# Main.net
KiCad netlist of a schematic drawn in Altium Designer
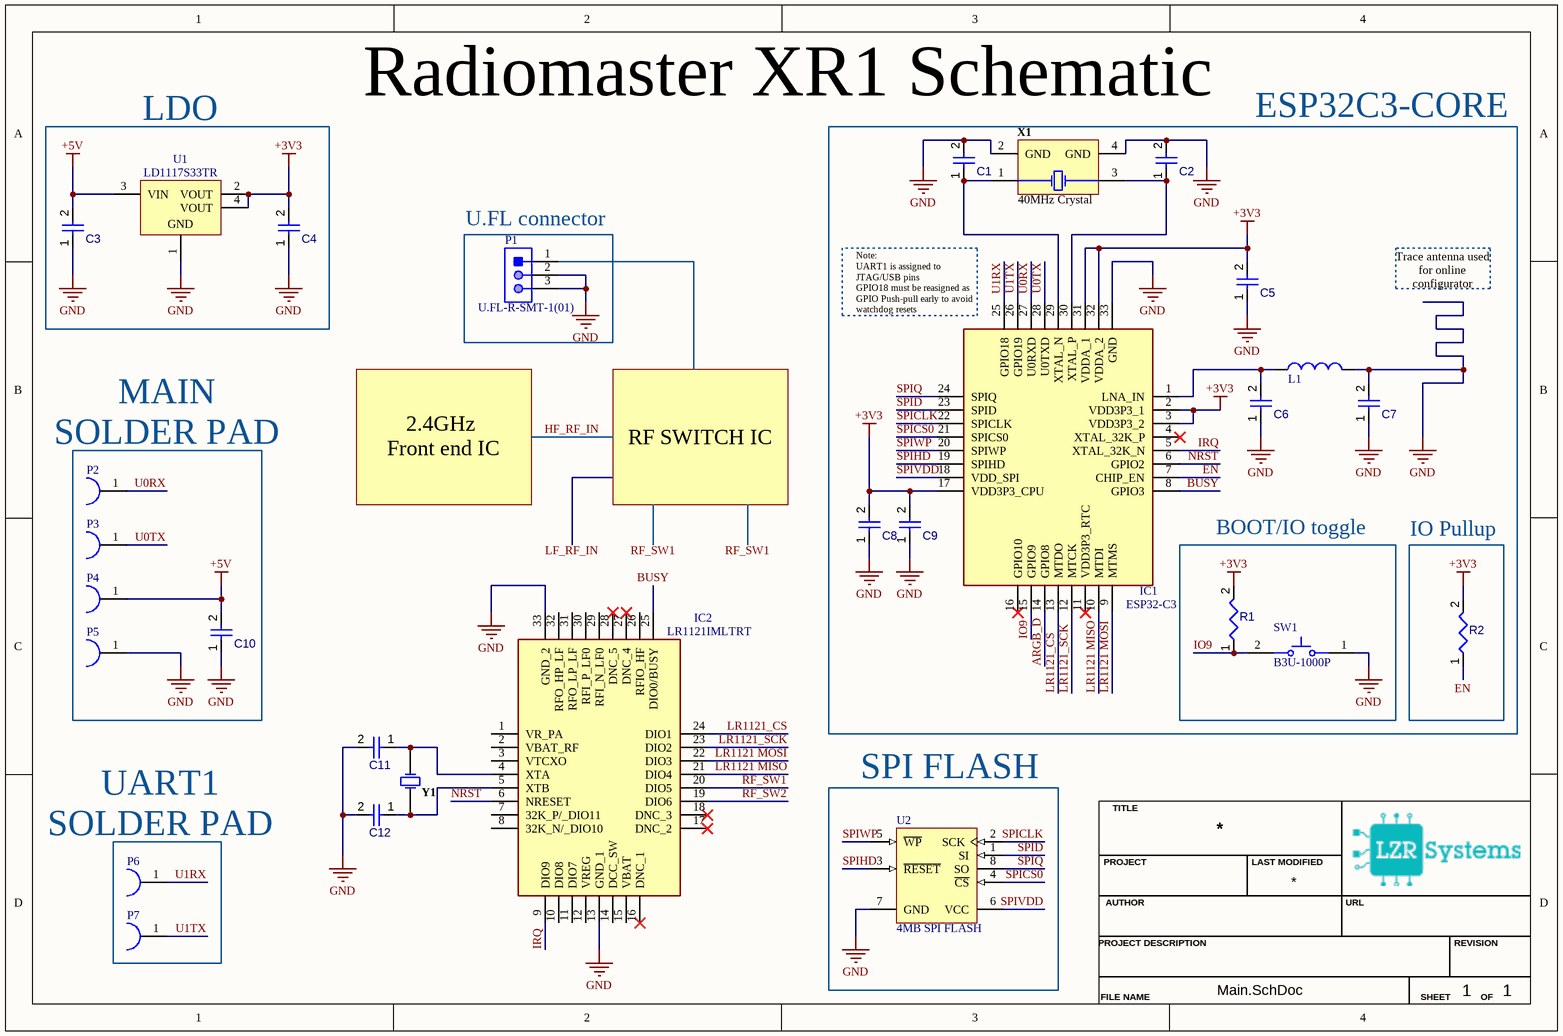
[diagram p0: Main.SchDoc]

(export (version "E")
  (design (tool "Eeschema 10.0.6"))
  (components
    (comp (ref "C1")
      (value "Capacitors")
      (description "Capacitor")
      (libsource (lib "Sandor Lazar") (part "CAP-NP-2"))
    )
    (comp (ref "C2")
      (value "Capacitors")
      (description "Capacitor")
      (libsource (lib "Sandor Lazar") (part "CAP-NP-2"))
    )
    (comp (ref "C3")
      (value "Capacitors")
      (description "Capacitor")
      (libsource (lib "Sandor Lazar") (part "CAP-NP-2"))
    )
    (comp (ref "C4")
      (value "Capacitors")
      (description "Capacitor")
      (libsource (lib "Sandor Lazar") (part "CAP-NP-2"))
    )
    (comp (ref "C5")
      (value "Capacitors")
      (description "Capacitor")
      (libsource (lib "Sandor Lazar") (part "CAP-NP-2"))
    )
    (comp (ref "C6")
      (value "Capacitors")
      (description "Capacitor")
      (libsource (lib "Sandor Lazar") (part "CAP-NP-2"))
    )
    (comp (ref "C7")
      (value "Capacitors")
      (description "Capacitor")
      (libsource (lib "Sandor Lazar") (part "CAP-NP-2"))
    )
    (comp (ref "C8")
      (value "Capacitors")
      (description "Capacitor")
      (libsource (lib "Sandor Lazar") (part "CAP-NP-2"))
    )
    (comp (ref "C9")
      (value "Capacitors")
      (description "Capacitor")
      (libsource (lib "Sandor Lazar") (part "CAP-NP-2"))
    )
    (comp (ref "C10")
      (value "Capacitors")
      (description "Capacitor")
      (libsource (lib "Sandor Lazar") (part "CAP-NP-2"))
    )
    (comp (ref "C11")
      (value "Capacitors")
      (description "Capacitor")
      (libsource (lib "Sandor Lazar") (part "CAP-NP-2"))
    )
    (comp (ref "C12")
      (value "Capacitors")
      (description "Capacitor")
      (libsource (lib "Sandor Lazar") (part "CAP-NP-2"))
    )
    (comp (ref "IC1")
      (value "ESP32-C3")
      (footprint "SamacSys:QFN50P500X500X90-33N-D")
      (description "Integrated Circuit")
      (fields (field (name "MOUSER PART NUMBER") "356-ESP32-C3"))
      (libsource (lib "SamacSys") (part "ESP32-C3"))
    )
    (comp (ref "IC2")
      (value "LR1121IMLTRT")
      (footprint "SamacSys:QFN50P500X500X100-33N-D")
      (description "Integrated Circuit")
      (fields (field (name "MOUSER PART NUMBER") "947-LR1121IMLTRT"))
      (libsource (lib "*") (part "LR1121IMLTRT"))
    )
    (comp (ref "L1") (value "Inductors") (libsource (lib "Sandor Lazar") (part "IND-2")))
    (comp (ref "P1")
      (value "U.FL-R-SMT-1(01)")
      (footprint "HRS-U.FL-R-SMT-3_V")
      (description "Rf Connectors / Coaxial Connectors SMT Ml Rec Au 50 Ohm W/anti Sldr Wicking")
      (libsource (lib "Sandor Lazar") (part "CN-1P-M-R3"))
    )
    (comp (ref "P2")
      (value "Solder Pad 2x1.5mm")
      (footprint "Solder Pad 2x1.5mm-Footprint-1")
      (description "Solder Pad 2x1.5mm, 0.5mm hole")
      (libsource (lib "Sandor Lazar") (part "Solder Pad 2x1.5mm"))
    )
    (comp (ref "P3")
      (value "Solder Pad 2x1.5mm")
      (footprint "Solder Pad 2x1.5mm-Footprint-1")
      (description "Solder Pad 2x1.5mm, 0.5mm hole")
      (libsource (lib "Sandor Lazar") (part "Solder Pad 2x1.5mm"))
    )
    (comp (ref "P4")
      (value "Solder Pad 2x1.5mm")
      (footprint "Solder Pad 2x1.5mm-Footprint-1")
      (description "Solder Pad 2x1.5mm, 0.5mm hole")
      (libsource (lib "Sandor Lazar") (part "Solder Pad 2x1.5mm"))
    )
    (comp (ref "P5")
      (value "Solder Pad 2x1.5mm")
      (footprint "Solder Pad 2x1.5mm-Footprint-1")
      (description "Solder Pad 2x1.5mm, 0.5mm hole")
      (libsource (lib "Sandor Lazar") (part "Solder Pad 2x1.5mm"))
    )
    (comp (ref "P6")
      (value "Solder Pad 2x1.5mm")
      (footprint "Solder Pad 2x1.5mm-Footprint-1")
      (description "Solder Pad 2x1.5mm, 0.5mm hole")
      (libsource (lib "Sandor Lazar") (part "Solder Pad 2x1.5mm"))
    )
    (comp (ref "P7")
      (value "Solder Pad 2x1.5mm")
      (footprint "Solder Pad 2x1.5mm-Footprint-1")
      (description "Solder Pad 2x1.5mm, 0.5mm hole")
      (libsource (lib "Sandor Lazar") (part "Solder Pad 2x1.5mm"))
    )
    (comp (ref "R1")
      (value "Resistors")
      (description "Resistor")
      (libsource (lib "Sandor Lazar") (part "RES-2"))
    )
    (comp (ref "R2")
      (value "Resistors")
      (description "Resistor")
      (libsource (lib "Sandor Lazar") (part "RES-2"))
    )
    (comp (ref "SW1")
      (value "B3U-1000P")
      (footprint "OMRON-B3U-1000_V")
      (description "Tactile Switch, SPST-NO, 0.05 A, 12 V, -25 to 70 degC, 2-Pin SMD, RoHS, Tape and Reel")
      (fields (field (name "MANUFACTURER") "Omron Electronic Components"))
      (libsource (lib "Sandor Lazar") (part "SW-SPST-NO-2"))
    )
    (comp (ref "U1")
      (value "LD1117S33TR")
      (footprint "STM-SOT-223_M")
      (fields (field (name "POWER") "12W") (field (name "MANUFACTURER") "STMicroelectronics"))
      (libsource (lib "Sandor Lazar") (part "STM-LD1117-SOT223-4"))
    )
    (comp (ref "U2")
      (value "4MB SPI FLASH")
      (footprint "ADST-8S1_M")
      (description "SPI Serial Flash Memory, 4-Mbit, 1.65 to 3.6 V, -40 to 85 degC, 8-Pin SOIC (8S1), RoHS, Tube")
      (fields (field (name "MANUFACTURER") "Adesto"))
      (libsource (lib "Sandor Lazar") (part "ADST-AT45DB041E-SOIC-8"))
    )
    (comp (ref "X1")
      (value "40MHz Crystal")
      (footprint "ABRA-ABM3B-4_V")
      (description "Ceramic SMD Crystal, 40 MHz, +/- 20 ppm, 18 pF, -20 to 70 degC, 4-Pin SMD, RoHS, Tape and Reel")
      (fields (field (name "TOLERANCE") "20ppm") (field (name "MANUFACTURER") "Abracon"))
      (libsource (lib "Sandor Lazar") (part "XTAL-1-3-4"))
    )
    (comp (ref "Y1")
      (value "Crystals & Oscillators")
      (description "Crystal")
      (libsource (lib "Sandor Lazar") (part "XTAL-2"))
    )
  )
  (nets
    (net (code "1") (name "+3V3") (class "Default")
      (node (ref "C4") (pin "2") (pinfunction "2_2") (pintype "passive"))
      (node (ref "C5") (pin "2") (pinfunction "2_2") (pintype "passive"))
      (node (ref "C8") (pin "2") (pinfunction "2_2") (pintype "passive"))
      (node (ref "C9") (pin "2") (pinfunction "2_2") (pintype "passive"))
      (node (ref "IC1") (pin "17") (pinfunction "VDD3P3_CPU_17") (pintype "passive"))
      (node (ref "IC1") (pin "2") (pinfunction "VDD3P3_1_2") (pintype "passive"))
      (node (ref "IC1") (pin "3") (pinfunction "VDD3P3_2_3") (pintype "passive"))
      (node (ref "IC1") (pin "31") (pinfunction "VDDA_1_31") (pintype "passive"))
      (node (ref "IC1") (pin "32") (pinfunction "VDDA_2_32") (pintype "passive"))
      (node (ref "R1") (pin "2") (pinfunction "2_2") (pintype "passive"))
      (node (ref "R2") (pin "2") (pinfunction "2_2") (pintype "passive"))
      (node (ref "U1") (pin "2") (pinfunction "VOUT_2") (pintype "power_in"))
      (node (ref "U1") (pin "4") (pinfunction "VOUT_4") (pintype "power_in"))
    )
    (net (code "2") (name "+5V") (class "Default")
      (node (ref "C10") (pin "2") (pinfunction "2_2") (pintype "passive"))
      (node (ref "C3") (pin "2") (pinfunction "2_2") (pintype "passive"))
      (node (ref "P4") (pin "1") (pinfunction "1_1") (pintype "passive"))
      (node (ref "U1") (pin "3") (pinfunction "VIN_3") (pintype "power_in"))
    )
    (net (code "3") (name "/ARGB_D") (class "Default")
      (node (ref "IC1") (pin "14") (pinfunction "GPIO8_14") (pintype "passive"))
    )
    (net (code "4") (name "/BUSY") (class "Default")
      (node (ref "IC1") (pin "8") (pinfunction "GPIO3_8") (pintype "passive"))
      (node (ref "IC2") (pin "25") (pinfunction "DIO0/BUSY_25") (pintype "passive"))
    )
    (net (code "5") (name "/EN") (class "Default")
      (node (ref "IC1") (pin "7") (pinfunction "CHIP_EN_7") (pintype "passive"))
      (node (ref "R2") (pin "1") (pinfunction "1_1") (pintype "passive"))
    )
    (net (code "7") (name "/IO9") (class "Default")
      (node (ref "IC1") (pin "15") (pinfunction "GPIO9_15") (pintype "passive"))
      (node (ref "R1") (pin "1") (pinfunction "1_1") (pintype "passive"))
      (node (ref "SW1") (pin "2") (pinfunction "2_2") (pintype "passive"))
    )
    (net (code "8") (name "/IRQ") (class "Default")
      (node (ref "IC1") (pin "5") (pinfunction "XTAL_32K_N_5") (pintype "passive"))
      (node (ref "IC2") (pin "9") (pinfunction "DIO9_9") (pintype "passive"))
    )
    (net (code "10") (name "/LR1121 MISO") (class "Default")
      (node (ref "IC1") (pin "10") (pinfunction "MTDI_10") (pintype "passive"))
      (node (ref "IC2") (pin "21") (pinfunction "DIO4_21") (pintype "passive"))
    )
    (net (code "11") (name "/LR1121 MOSI") (class "Default")
      (node (ref "IC1") (pin "9") (pinfunction "MTMS_9") (pintype "passive"))
      (node (ref "IC2") (pin "22") (pinfunction "DIO3_22") (pintype "passive"))
    )
    (net (code "12") (name "/LR1121_CS") (class "Default")
      (node (ref "IC1") (pin "13") (pinfunction "MTDO_13") (pintype "passive"))
      (node (ref "IC2") (pin "24") (pinfunction "DIO1_24") (pintype "passive"))
    )
    (net (code "13") (name "/LR1121_SCK") (class "Default")
      (node (ref "IC1") (pin "12") (pinfunction "MTCK_12") (pintype "passive"))
      (node (ref "IC2") (pin "23") (pinfunction "DIO2_23") (pintype "passive"))
    )
    (net (code "14") (name "/NRST") (class "Default")
      (node (ref "IC1") (pin "6") (pinfunction "GPIO2_6") (pintype "passive"))
      (node (ref "IC2") (pin "6") (pinfunction "NRESET_6") (pintype "passive"))
    )
    (net (code "15") (name "/RF_SW1") (class "Default")
      (node (ref "IC2") (pin "20") (pinfunction "DIO5_20") (pintype "passive"))
    )
    (net (code "16") (name "/RF_SW2") (class "Default")
      (node (ref "IC2") (pin "19") (pinfunction "DIO6_19") (pintype "passive"))
    )
    (net (code "17") (name "/SPICLK") (class "Default")
      (node (ref "IC1") (pin "22") (pinfunction "SPICLK_22") (pintype "passive"))
      (node (ref "U2") (pin "2") (pinfunction "SCK_2") (pintype "input"))
    )
    (net (code "18") (name "/SPICS0") (class "Default")
      (node (ref "IC1") (pin "21") (pinfunction "SPICS0_21") (pintype "passive"))
      (node (ref "U2") (pin "4") (pinfunction "~{CS}_4") (pintype "input"))
    )
    (net (code "19") (name "/SPID") (class "Default")
      (node (ref "IC1") (pin "23") (pinfunction "SPID_23") (pintype "passive"))
      (node (ref "U2") (pin "1") (pinfunction "SI_1") (pintype "input"))
    )
    (net (code "20") (name "/SPIHD") (class "Default")
      (node (ref "IC1") (pin "19") (pinfunction "SPIHD_19") (pintype "passive"))
      (node (ref "U2") (pin "3") (pinfunction "~{RESET}_3") (pintype "input"))
    )
    (net (code "21") (name "/SPIQ") (class "Default")
      (node (ref "IC1") (pin "24") (pinfunction "SPIQ_24") (pintype "passive"))
      (node (ref "U2") (pin "8") (pinfunction "SO_8") (pintype "tri_state"))
    )
    (net (code "22") (name "/SPIVDD") (class "Default")
      (node (ref "IC1") (pin "18") (pinfunction "VDD_SPI_18") (pintype "passive"))
      (node (ref "U2") (pin "6") (pinfunction "VCC_6") (pintype "power_in"))
    )
    (net (code "23") (name "/SPIWP") (class "Default")
      (node (ref "IC1") (pin "20") (pinfunction "SPIWP_20") (pintype "passive"))
      (node (ref "U2") (pin "5") (pinfunction "~{WP}_5") (pintype "input"))
    )
    (net (code "24") (name "/U0RX") (class "Default")
      (node (ref "IC1") (pin "27") (pinfunction "U0RXD_27") (pintype "passive"))
      (node (ref "P2") (pin "1") (pinfunction "1_1") (pintype "passive"))
    )
    (net (code "25") (name "/U0TX") (class "Default")
      (node (ref "IC1") (pin "28") (pinfunction "U0TXD_28") (pintype "passive"))
      (node (ref "P3") (pin "1") (pinfunction "1_1") (pintype "passive"))
    )
    (net (code "26") (name "/U1RX") (class "Default")
      (node (ref "IC1") (pin "25") (pinfunction "GPIO18_25") (pintype "passive"))
      (node (ref "P6") (pin "1") (pinfunction "1_1") (pintype "passive"))
    )
    (net (code "27") (name "/U1TX") (class "Default")
      (node (ref "IC1") (pin "26") (pinfunction "GPIO19_26") (pintype "passive"))
      (node (ref "P7") (pin "1") (pinfunction "1_1") (pintype "passive"))
    )
    (net (code "28") (name "GND") (class "Default")
      (node (ref "C1") (pin "2") (pinfunction "2_2") (pintype "passive"))
      (node (ref "C10") (pin "1") (pinfunction "1_1") (pintype "passive"))
      (node (ref "C11") (pin "2") (pinfunction "2_2") (pintype "passive"))
      (node (ref "C12") (pin "2") (pinfunction "2_2") (pintype "passive"))
      (node (ref "C2") (pin "2") (pinfunction "2_2") (pintype "passive"))
      (node (ref "C3") (pin "1") (pinfunction "1_1") (pintype "passive"))
      (node (ref "C4") (pin "1") (pinfunction "1_1") (pintype "passive"))
      (node (ref "C5") (pin "1") (pinfunction "1_1") (pintype "passive"))
      (node (ref "C6") (pin "1") (pinfunction "1_1") (pintype "passive"))
      (node (ref "C7") (pin "1") (pinfunction "1_1") (pintype "passive"))
      (node (ref "C7") (pin "2") (pinfunction "2_2") (pintype "passive"))
      (node (ref "C8") (pin "1") (pinfunction "1_1") (pintype "passive"))
      (node (ref "C9") (pin "1") (pinfunction "1_1") (pintype "passive"))
      (node (ref "IC1") (pin "33") (pinfunction "GND_33") (pintype "passive"))
      (node (ref "IC2") (pin "13") (pinfunction "GND_1_13") (pintype "passive"))
      (node (ref "IC2") (pin "33") (pinfunction "GND_2_33") (pintype "passive"))
      (node (ref "L1") (pin "1") (pinfunction "1_1") (pintype "passive"))
      (node (ref "P1") (pin "2") (pinfunction "2_2") (pintype "passive"))
      (node (ref "P1") (pin "3") (pinfunction "3_3") (pintype "passive"))
      (node (ref "P5") (pin "1") (pinfunction "1_1") (pintype "passive"))
      (node (ref "SW1") (pin "1") (pinfunction "1_1") (pintype "passive"))
      (node (ref "U1") (pin "1") (pinfunction "GND_1") (pintype "power_in"))
      (node (ref "U2") (pin "7") (pinfunction "GND_7") (pintype "power_in"))
      (node (ref "X1") (pin "2") (pinfunction "GND_2") (pintype "power_in"))
      (node (ref "X1") (pin "4") (pinfunction "GND_4") (pintype "power_in"))
    )
    (net (code "29") (name "Net-(IC1-LNA_IN)") (class "Default")
      (node (ref "C6") (pin "2") (pinfunction "2_2") (pintype "passive"))
      (node (ref "IC1") (pin "1") (pinfunction "LNA_IN_1") (pintype "passive"))
      (node (ref "L1") (pin "2") (pinfunction "2_2") (pintype "passive"))
    )
    (net (code "30") (name "Net-(IC1-XTAL_N)") (class "Default")
      (node (ref "C1") (pin "1") (pinfunction "1_1") (pintype "passive"))
      (node (ref "IC1") (pin "29") (pinfunction "XTAL_N_29") (pintype "passive"))
      (node (ref "X1") (pin "1") (pinfunction "X1_1") (pintype "passive"))
    )
    (net (code "31") (name "Net-(IC1-XTAL_P)") (class "Default")
      (node (ref "C2") (pin "1") (pinfunction "1_1") (pintype "passive"))
      (node (ref "IC1") (pin "30") (pinfunction "XTAL_P_30") (pintype "passive"))
      (node (ref "X1") (pin "3") (pinfunction "X2_3") (pintype "passive"))
    )
    (net (code "32") (name "Net-(IC2-XTA)") (class "Default")
      (node (ref "C11") (pin "1") (pinfunction "1_1") (pintype "passive"))
      (node (ref "IC2") (pin "4") (pinfunction "XTA_4") (pintype "passive"))
      (node (ref "Y1") (pin "2") (pinfunction "2_2") (pintype "passive"))
    )
    (net (code "33") (name "Net-(IC2-XTB)") (class "Default")
      (node (ref "C12") (pin "1") (pinfunction "1_1") (pintype "passive"))
      (node (ref "IC2") (pin "5") (pinfunction "XTB_5") (pintype "passive"))
      (node (ref "Y1") (pin "1") (pinfunction "1_1") (pintype "passive"))
    )
    (net (code "34") (name "unconnected-(IC1-GPIO10-Pad16)") (class "Default")
      (node (ref "IC1") (pin "16") (pinfunction "GPIO10_16") (pintype "passive+no_connect"))
    )
    (net (code "35") (name "unconnected-(IC1-VDD3P3_RTC-Pad11)") (class "Default")
      (node (ref "IC1") (pin "11") (pinfunction "VDD3P3_RTC_11") (pintype "passive+no_connect"))
    )
    (net (code "36") (name "unconnected-(IC1-XTAL_32K_P-Pad4)") (class "Default")
      (node (ref "IC1") (pin "4") (pinfunction "XTAL_32K_P_4") (pintype "passive+no_connect"))
    )
    (net (code "37") (name "unconnected-(IC2-32K_N{slash}_DIO10-Pad8)") (class "Default")
      (node (ref "IC2") (pin "8") (pinfunction "32K_N/_DIO10_8") (pintype "passive"))
    )
    (net (code "38") (name "unconnected-(IC2-32K_P{slash}_DIO11-Pad7)") (class "Default")
      (node (ref "IC2") (pin "7") (pinfunction "32K_P/_DIO11_7") (pintype "passive"))
    )
    (net (code "39") (name "unconnected-(IC2-DCC_SW-Pad14)") (class "Default")
      (node (ref "IC2") (pin "14") (pinfunction "DCC_SW_14") (pintype "passive"))
    )
    (net (code "40") (name "unconnected-(IC2-DIO7-Pad11)") (class "Default")
      (node (ref "IC2") (pin "11") (pinfunction "DIO7_11") (pintype "passive"))
    )
    (net (code "41") (name "unconnected-(IC2-DIO8-Pad10)") (class "Default")
      (node (ref "IC2") (pin "10") (pinfunction "DIO8_10") (pintype "passive"))
    )
    (net (code "42") (name "unconnected-(IC2-DNC_1-Pad16)") (class "Default")
      (node (ref "IC2") (pin "16") (pinfunction "DNC_1_16") (pintype "passive+no_connect"))
    )
    (net (code "43") (name "unconnected-(IC2-DNC_2-Pad17)") (class "Default")
      (node (ref "IC2") (pin "17") (pinfunction "DNC_2_17") (pintype "passive+no_connect"))
    )
    (net (code "44") (name "unconnected-(IC2-DNC_3-Pad18)") (class "Default")
      (node (ref "IC2") (pin "18") (pinfunction "DNC_3_18") (pintype "passive+no_connect"))
    )
    (net (code "45") (name "unconnected-(IC2-DNC_4-Pad27)") (class "Default")
      (node (ref "IC2") (pin "27") (pinfunction "DNC_4_27") (pintype "passive+no_connect"))
    )
    (net (code "46") (name "unconnected-(IC2-DNC_5-Pad28)") (class "Default")
      (node (ref "IC2") (pin "28") (pinfunction "DNC_5_28") (pintype "passive+no_connect"))
    )
    (net (code "47") (name "unconnected-(IC2-RFIO_HF-Pad26)") (class "Default")
      (node (ref "IC2") (pin "26") (pinfunction "RFIO_HF_26") (pintype "passive"))
    )
    (net (code "48") (name "unconnected-(IC2-RFI_N_LF0-Pad29)") (class "Default")
      (node (ref "IC2") (pin "29") (pinfunction "RFI_N_LF0_29") (pintype "passive"))
    )
    (net (code "49") (name "unconnected-(IC2-RFI_P_LF0-Pad30)") (class "Default")
      (node (ref "IC2") (pin "30") (pinfunction "RFI_P_LF0_30") (pintype "passive"))
    )
    (net (code "50") (name "unconnected-(IC2-RFO_HP_LF-Pad32)") (class "Default")
      (node (ref "IC2") (pin "32") (pinfunction "RFO_HP_LF_32") (pintype "passive"))
    )
    (net (code "51") (name "unconnected-(IC2-RFO_LP_LF-Pad31)") (class "Default")
      (node (ref "IC2") (pin "31") (pinfunction "RFO_LP_LF_31") (pintype "passive"))
    )
    (net (code "52") (name "unconnected-(IC2-VBAT-Pad15)") (class "Default")
      (node (ref "IC2") (pin "15") (pinfunction "VBAT_15") (pintype "passive"))
    )
    (net (code "53") (name "unconnected-(IC2-VBAT_RF-Pad2)") (class "Default")
      (node (ref "IC2") (pin "2") (pinfunction "VBAT_RF_2") (pintype "passive"))
    )
    (net (code "54") (name "unconnected-(IC2-VREG-Pad12)") (class "Default")
      (node (ref "IC2") (pin "12") (pinfunction "VREG_12") (pintype "passive"))
    )
    (net (code "55") (name "unconnected-(IC2-VR_PA-Pad1)") (class "Default")
      (node (ref "IC2") (pin "1") (pinfunction "VR_PA_1") (pintype "passive"))
    )
    (net (code "56") (name "unconnected-(IC2-VTCXO-Pad3)") (class "Default")
      (node (ref "IC2") (pin "3") (pinfunction "VTCXO_3") (pintype "passive"))
    )
    (net (code "57") (name "unconnected-(P1-Pad1)") (class "Default")
      (node (ref "P1") (pin "1") (pinfunction "1_1") (pintype "passive"))
    )
  )
)
